# line-sensor.net
KiCad netlist of a schematic drawn in EAGLE
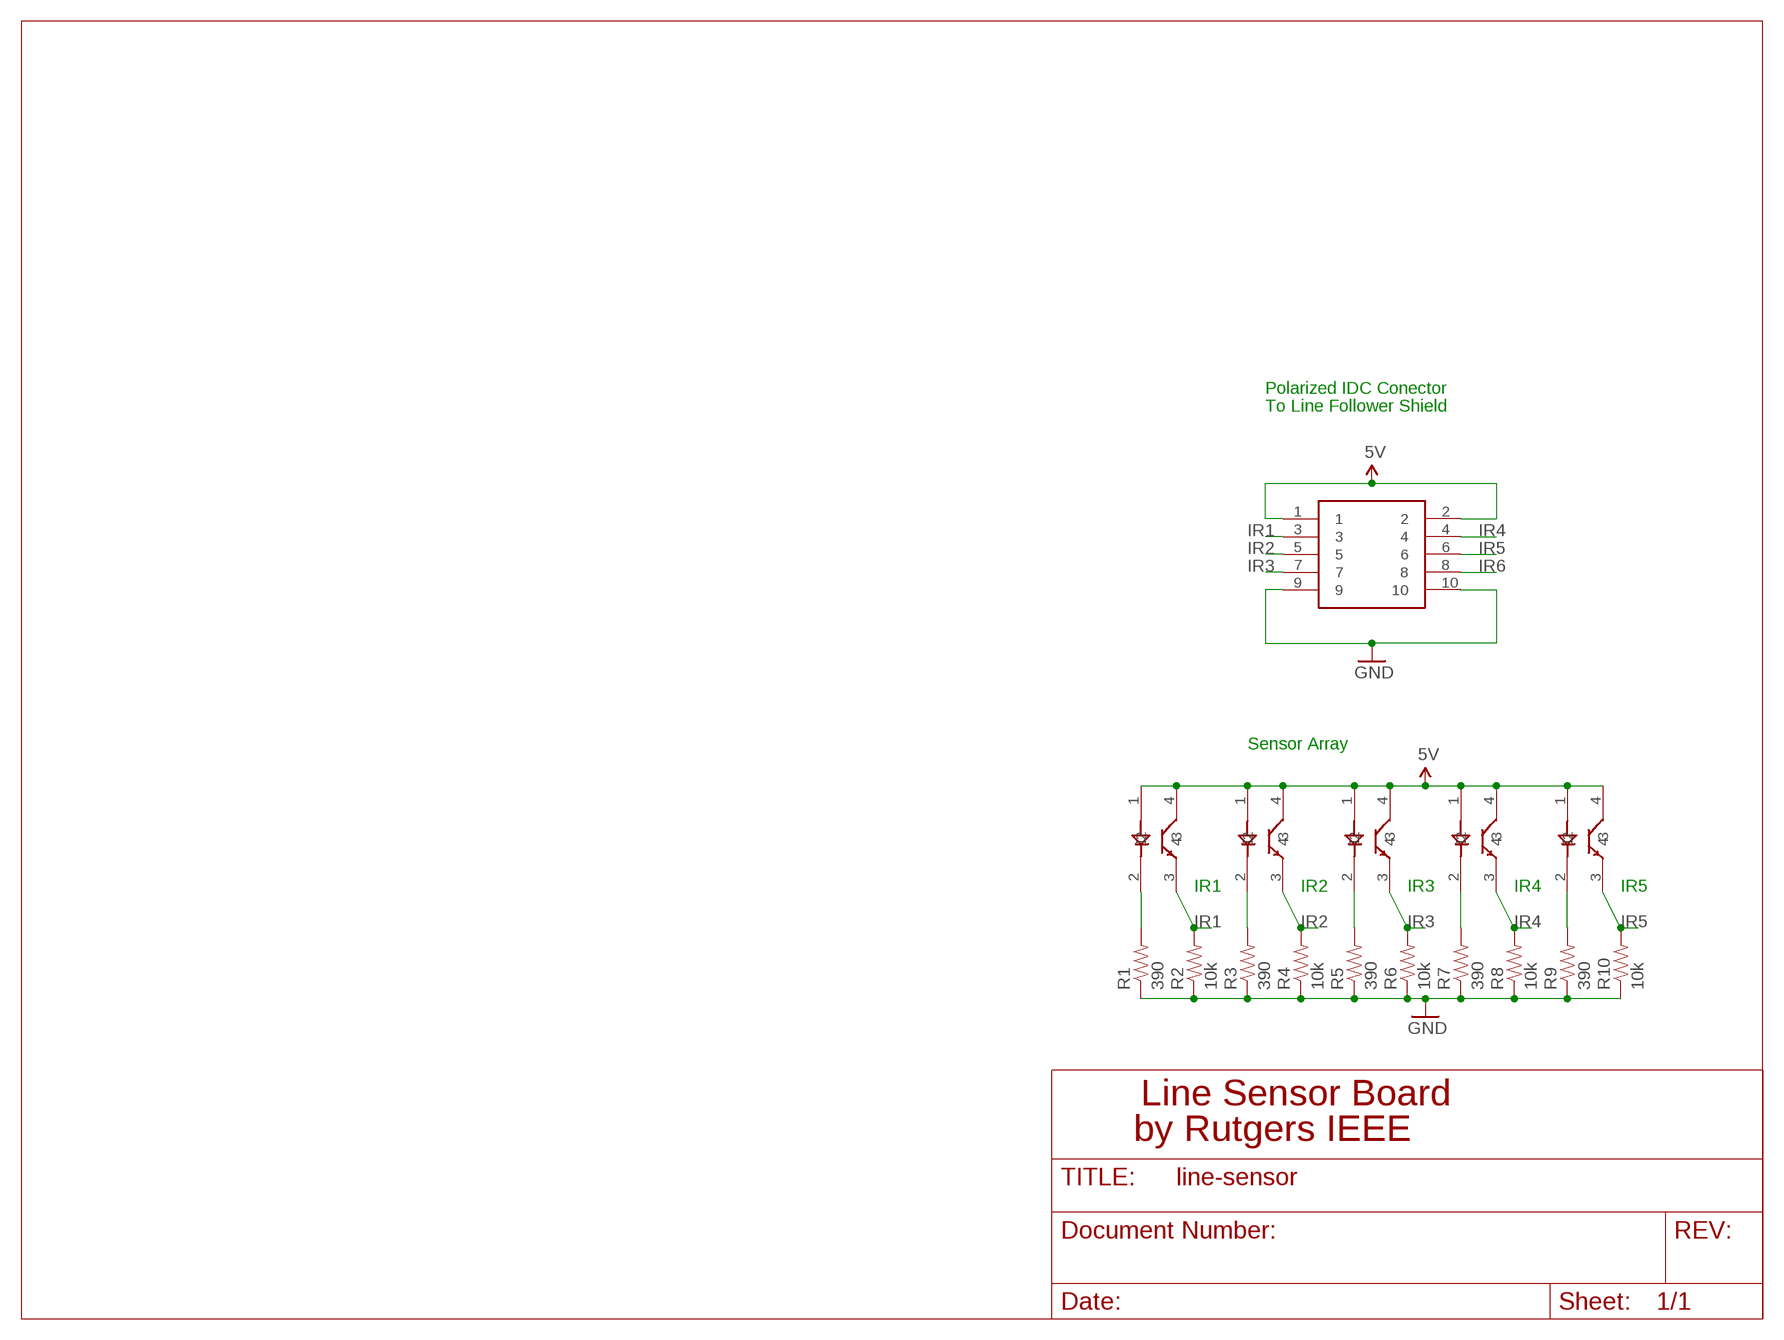
[diagram p0: schematic, sheet 1]

(export (version "E")
  (design (tool "Eeschema 10.0.6"))
  (components
    (comp (ref "R1")
      (value "390")
      (footprint "eagle-import:AXIAL-0.3")
      (libsource (lib "eagle-import") (part "RESISTORPTH1"))
    )
    (comp (ref "R2")
      (value "10k")
      (footprint "eagle-import:AXIAL-0.3")
      (libsource (lib "eagle-import") (part "RESISTORPTH1"))
    )
    (comp (ref "R3")
      (value "390")
      (footprint "eagle-import:AXIAL-0.3")
      (libsource (lib "eagle-import") (part "RESISTORPTH1"))
    )
    (comp (ref "R4")
      (value "10k")
      (footprint "eagle-import:AXIAL-0.3")
      (libsource (lib "eagle-import") (part "RESISTORPTH1"))
    )
    (comp (ref "R5")
      (value "390")
      (footprint "eagle-import:AXIAL-0.3")
      (libsource (lib "eagle-import") (part "RESISTORPTH1"))
    )
    (comp (ref "R6")
      (value "10k")
      (footprint "eagle-import:AXIAL-0.3")
      (libsource (lib "eagle-import") (part "RESISTORPTH1"))
    )
    (comp (ref "R7")
      (value "390")
      (footprint "eagle-import:AXIAL-0.3")
      (libsource (lib "eagle-import") (part "RESISTORPTH1"))
    )
    (comp (ref "R8")
      (value "10k")
      (footprint "eagle-import:AXIAL-0.3")
      (libsource (lib "eagle-import") (part "RESISTORPTH1"))
    )
    (comp (ref "R9")
      (value "390")
      (footprint "eagle-import:AXIAL-0.3")
      (libsource (lib "eagle-import") (part "RESISTORPTH1"))
    )
    (comp (ref "R10")
      (value "10k")
      (footprint "eagle-import:AXIAL-0.3")
      (libsource (lib "eagle-import") (part "RESISTORPTH1"))
    )
    (comp (ref "U$1")
      (value "IR1")
      (footprint "eagle-import:RPR220")
      (libsource (lib "eagle-import") (part "RPR220"))
    )
    (comp (ref "U$2")
      (value "IR2")
      (footprint "eagle-import:RPR220")
      (libsource (lib "eagle-import") (part "RPR220"))
    )
    (comp (ref "U$3")
      (value "IR3")
      (footprint "eagle-import:RPR220")
      (libsource (lib "eagle-import") (part "RPR220"))
    )
    (comp (ref "U$4")
      (value "IR4")
      (footprint "eagle-import:RPR220")
      (libsource (lib "eagle-import") (part "RPR220"))
    )
    (comp (ref "U$5")
      (value "IR5")
      (footprint "eagle-import:RPR220")
      (libsource (lib "eagle-import") (part "RPR220"))
    )
    (comp (ref "U$8")
      (value "2X5-PHEADER")
      (footprint "eagle-import:2X5-SHROUDED-HEADER")
      (libsource (lib "eagle-import") (part "2X5-PHEADER"))
    )
  )
  (nets
    (net (code "1") (name "/IR1") (class "Default")
      (node (ref "R2") (pin "P$2") (pinfunction "2_P$2") (pintype "passive"))
      (node (ref "U$1") (pin "3") (pinfunction "3_3") (pintype "bidirectional"))
      (node (ref "U$8") (pin "3") (pinfunction "3_3") (pintype "bidirectional"))
    )
    (net (code "2") (name "/IR2") (class "Default")
      (node (ref "R4") (pin "P$2") (pinfunction "2_P$2") (pintype "passive"))
      (node (ref "U$2") (pin "3") (pinfunction "3_3") (pintype "bidirectional"))
      (node (ref "U$8") (pin "5") (pinfunction "5_5") (pintype "bidirectional"))
    )
    (net (code "3") (name "/IR3") (class "Default")
      (node (ref "R6") (pin "P$2") (pinfunction "2_P$2") (pintype "passive"))
      (node (ref "U$3") (pin "3") (pinfunction "3_3") (pintype "bidirectional"))
      (node (ref "U$8") (pin "7") (pinfunction "7_7") (pintype "bidirectional"))
    )
    (net (code "4") (name "/IR4") (class "Default")
      (node (ref "R8") (pin "P$2") (pinfunction "2_P$2") (pintype "passive"))
      (node (ref "U$4") (pin "3") (pinfunction "3_3") (pintype "bidirectional"))
      (node (ref "U$8") (pin "4") (pinfunction "4_4") (pintype "bidirectional"))
    )
    (net (code "5") (name "/IR5") (class "Default")
      (node (ref "R10") (pin "P$2") (pinfunction "2_P$2") (pintype "passive"))
      (node (ref "U$5") (pin "3") (pinfunction "3_3") (pintype "bidirectional"))
      (node (ref "U$8") (pin "6") (pinfunction "6_6") (pintype "bidirectional"))
    )
    (net (code "6") (name "/IR6") (class "Default")
      (node (ref "U$8") (pin "8") (pinfunction "8_8") (pintype "bidirectional"))
    )
    (net (code "7") (name "5V") (class "Default")
      (node (ref "U$1") (pin "1") (pinfunction "1_1") (pintype "bidirectional"))
      (node (ref "U$1") (pin "4") (pinfunction "4_4") (pintype "bidirectional"))
      (node (ref "U$2") (pin "1") (pinfunction "1_1") (pintype "bidirectional"))
      (node (ref "U$2") (pin "4") (pinfunction "4_4") (pintype "bidirectional"))
      (node (ref "U$3") (pin "1") (pinfunction "1_1") (pintype "bidirectional"))
      (node (ref "U$3") (pin "4") (pinfunction "4_4") (pintype "bidirectional"))
      (node (ref "U$4") (pin "1") (pinfunction "1_1") (pintype "bidirectional"))
      (node (ref "U$4") (pin "4") (pinfunction "4_4") (pintype "bidirectional"))
      (node (ref "U$5") (pin "1") (pinfunction "1_1") (pintype "bidirectional"))
      (node (ref "U$5") (pin "4") (pinfunction "4_4") (pintype "bidirectional"))
      (node (ref "U$8") (pin "1") (pinfunction "1_1") (pintype "bidirectional"))
      (node (ref "U$8") (pin "2") (pinfunction "2_2") (pintype "bidirectional"))
    )
    (net (code "8") (name "GND") (class "Default")
      (node (ref "R1") (pin "P$1") (pinfunction "1_P$1") (pintype "passive"))
      (node (ref "R10") (pin "P$1") (pinfunction "1_P$1") (pintype "passive"))
      (node (ref "R2") (pin "P$1") (pinfunction "1_P$1") (pintype "passive"))
      (node (ref "R3") (pin "P$1") (pinfunction "1_P$1") (pintype "passive"))
      (node (ref "R4") (pin "P$1") (pinfunction "1_P$1") (pintype "passive"))
      (node (ref "R5") (pin "P$1") (pinfunction "1_P$1") (pintype "passive"))
      (node (ref "R6") (pin "P$1") (pinfunction "1_P$1") (pintype "passive"))
      (node (ref "R7") (pin "P$1") (pinfunction "1_P$1") (pintype "passive"))
      (node (ref "R8") (pin "P$1") (pinfunction "1_P$1") (pintype "passive"))
      (node (ref "R9") (pin "P$1") (pinfunction "1_P$1") (pintype "passive"))
      (node (ref "U$8") (pin "10") (pinfunction "10_10") (pintype "bidirectional"))
      (node (ref "U$8") (pin "9") (pinfunction "9_9") (pintype "bidirectional"))
    )
    (net (code "9") (name "Net-(R1-2)") (class "Default")
      (node (ref "R1") (pin "P$2") (pinfunction "2_P$2") (pintype "passive"))
      (node (ref "U$1") (pin "2") (pinfunction "2_2") (pintype "bidirectional"))
    )
    (net (code "10") (name "Net-(R3-2)") (class "Default")
      (node (ref "R3") (pin "P$2") (pinfunction "2_P$2") (pintype "passive"))
      (node (ref "U$2") (pin "2") (pinfunction "2_2") (pintype "bidirectional"))
    )
    (net (code "11") (name "Net-(R5-2)") (class "Default")
      (node (ref "R5") (pin "P$2") (pinfunction "2_P$2") (pintype "passive"))
      (node (ref "U$3") (pin "2") (pinfunction "2_2") (pintype "bidirectional"))
    )
    (net (code "12") (name "Net-(R7-2)") (class "Default")
      (node (ref "R7") (pin "P$2") (pinfunction "2_P$2") (pintype "passive"))
      (node (ref "U$4") (pin "2") (pinfunction "2_2") (pintype "bidirectional"))
    )
    (net (code "13") (name "Net-(R9-2)") (class "Default")
      (node (ref "R9") (pin "P$2") (pinfunction "2_P$2") (pintype "passive"))
      (node (ref "U$5") (pin "2") (pinfunction "2_2") (pintype "bidirectional"))
    )
  )
)
